# Channel.net
KiCad netlist of a schematic drawn in Altium Designer
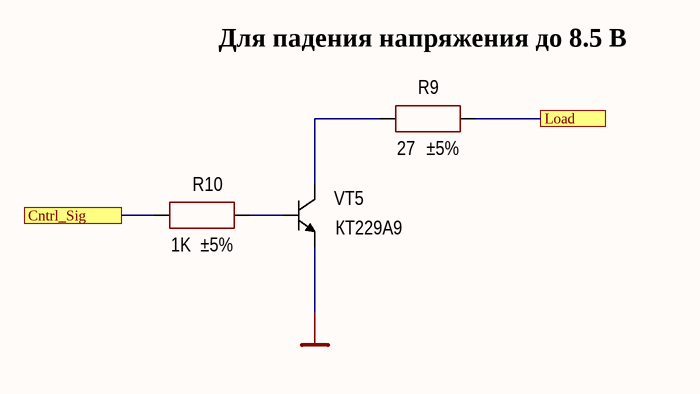
[diagram p0: Channel.SchDoc]

(export (version "E")
  (design (tool "Eeschema 10.0.6"))
  (components
    (comp (ref "R9")
      (value "27")
      (footprint "RES: 0805")
      (fields
        (field (name "MANUFACTURER") "Yageo")
        (field (name "PARTNUMBER") "RC0805JR-07100RL")
        (field (name "VALUEMANUFACTURERPARTNUMBER") "Resistor film, 27, ±5%, 0805, 0.125W, -55...+125°C")
        (field (name "TOLERANCE") "±5%")
      )
      (libsource (lib "Resistor") (part "Resistor_0805"))
    )
    (comp (ref "R10")
      (value "1K")
      (footprint "RES: 0805")
      (fields
        (field (name "MANUFACTURER") "Yageo")
        (field (name "PARTNUMBER") "RC0805JR-07100RL")
        (field (name "VALUEMANUFACTURERPARTNUMBER") "Resistor film, 1K, ±5%, 0805, 0.125W, -55...+125°C")
        (field (name "TOLERANCE") "±5%")
      )
      (libsource (lib "Resistor") (part "Resistor_0805"))
    )
    (comp (ref "VT5")
      (value "~")
      (footprint "SOT23")
      (fields
        (field (name "MANUFACTURER") "ON Semiconductor")
        (field (name "VALUEMANUFACTURERPARTNUMBER") "NPN transistor, 45V, 100mA, 100MHz, 300mW, 0.6V, 420, SOT-23, -55...+125°C")
        (field (name "PARTNUMBER") "КТ229А9")
      )
      (libsource (lib "Transistor") (part "BJT_NPN_132"))
    )
  )
  (nets
    (net (code "1") (name "/Cntrl_Sig") (class "Default")
      (node (ref "R10") (pin "1") (pinfunction "1_1") (pintype "passive"))
    )
    (net (code "2") (name "/Load") (class "Default")
      (node (ref "R9") (pin "2") (pinfunction "2_2") (pintype "passive"))
    )
    (net (code "3") (name "GND") (class "Default")
      (node (ref "VT5") (pin "2") (pinfunction "E_2") (pintype "passive"))
    )
    (net (code "4") (name "Net-(VT5-B)") (class "Default")
      (node (ref "R10") (pin "2") (pinfunction "2_2") (pintype "passive"))
      (node (ref "VT5") (pin "1") (pinfunction "B_1") (pintype "passive"))
    )
    (net (code "5") (name "Net-(VT5-C)") (class "Default")
      (node (ref "R9") (pin "1") (pinfunction "1_1") (pintype "passive"))
      (node (ref "VT5") (pin "3") (pinfunction "C_3") (pintype "passive"))
    )
  )
)
